# lisa_m.net
KiCad netlist of a schematic drawn in EAGLE
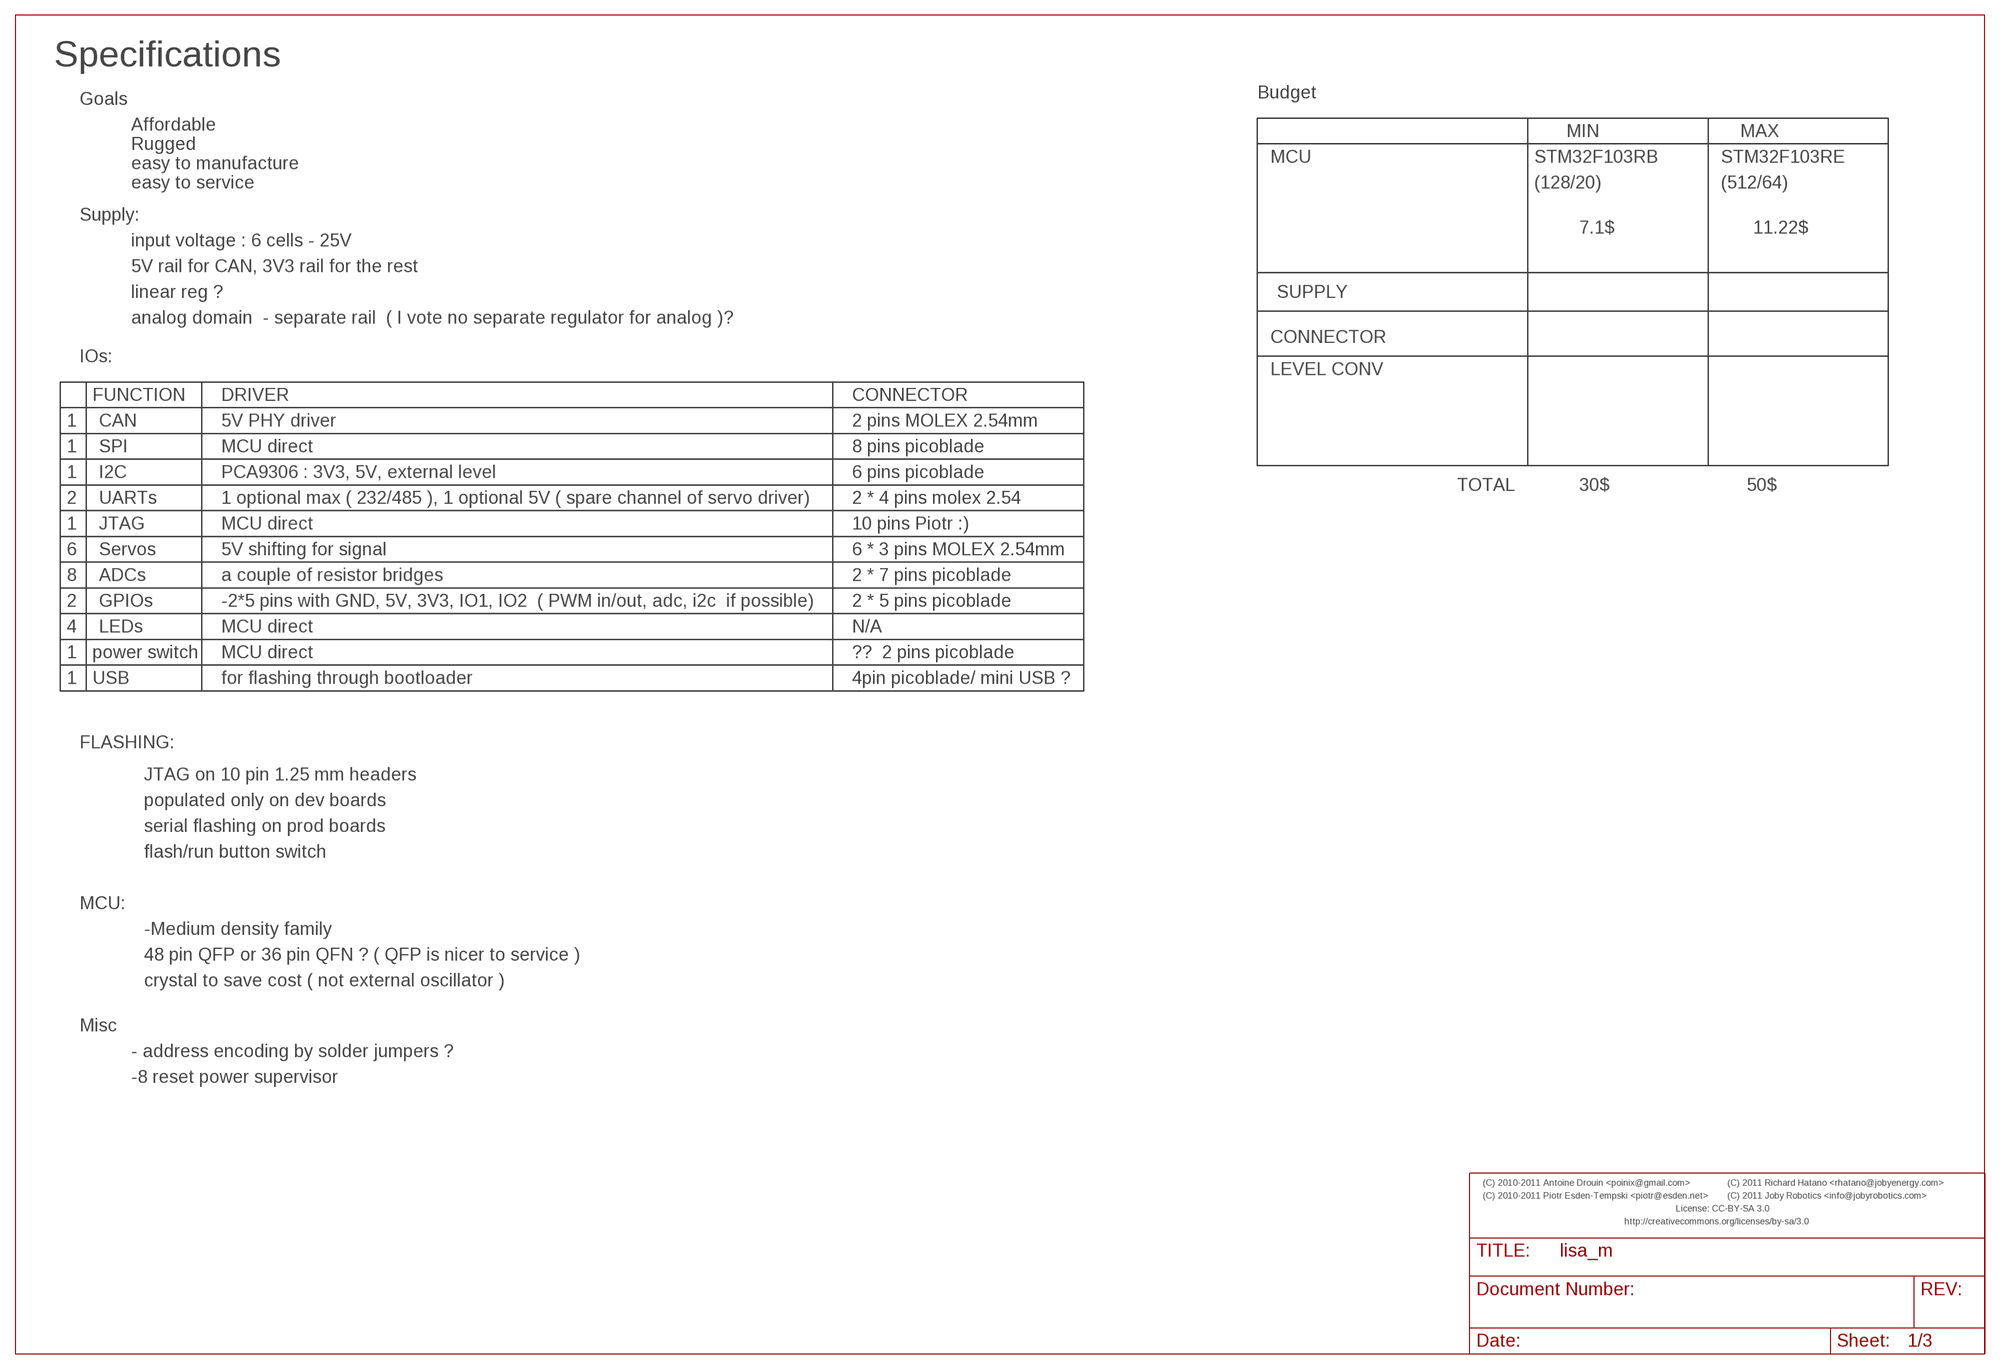
[diagram p0: schematic, sheet 1]
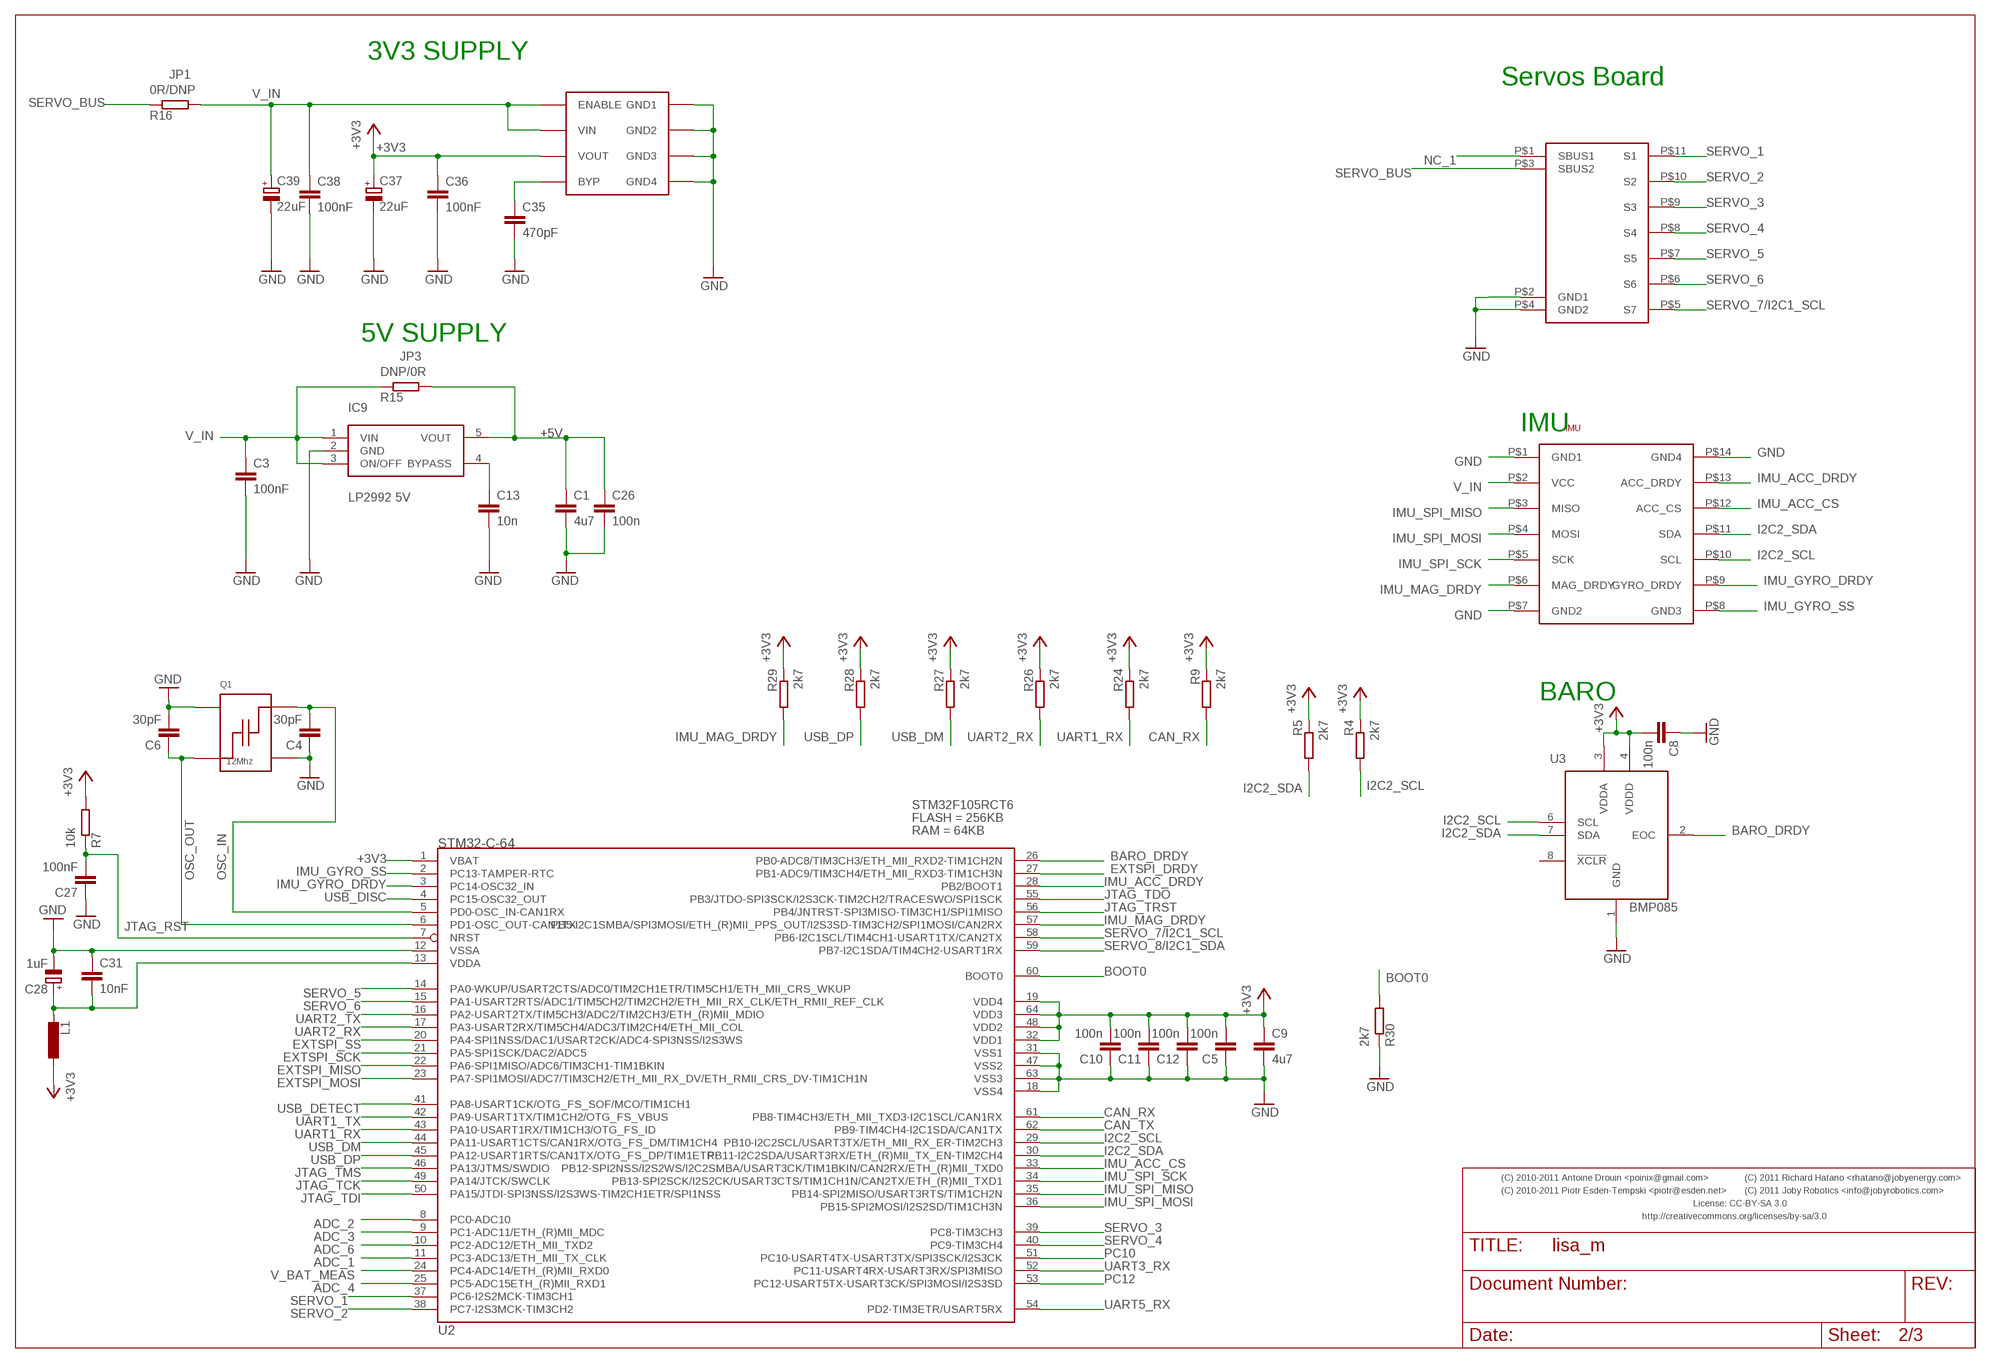
[diagram p1: schematic, sheet 2]
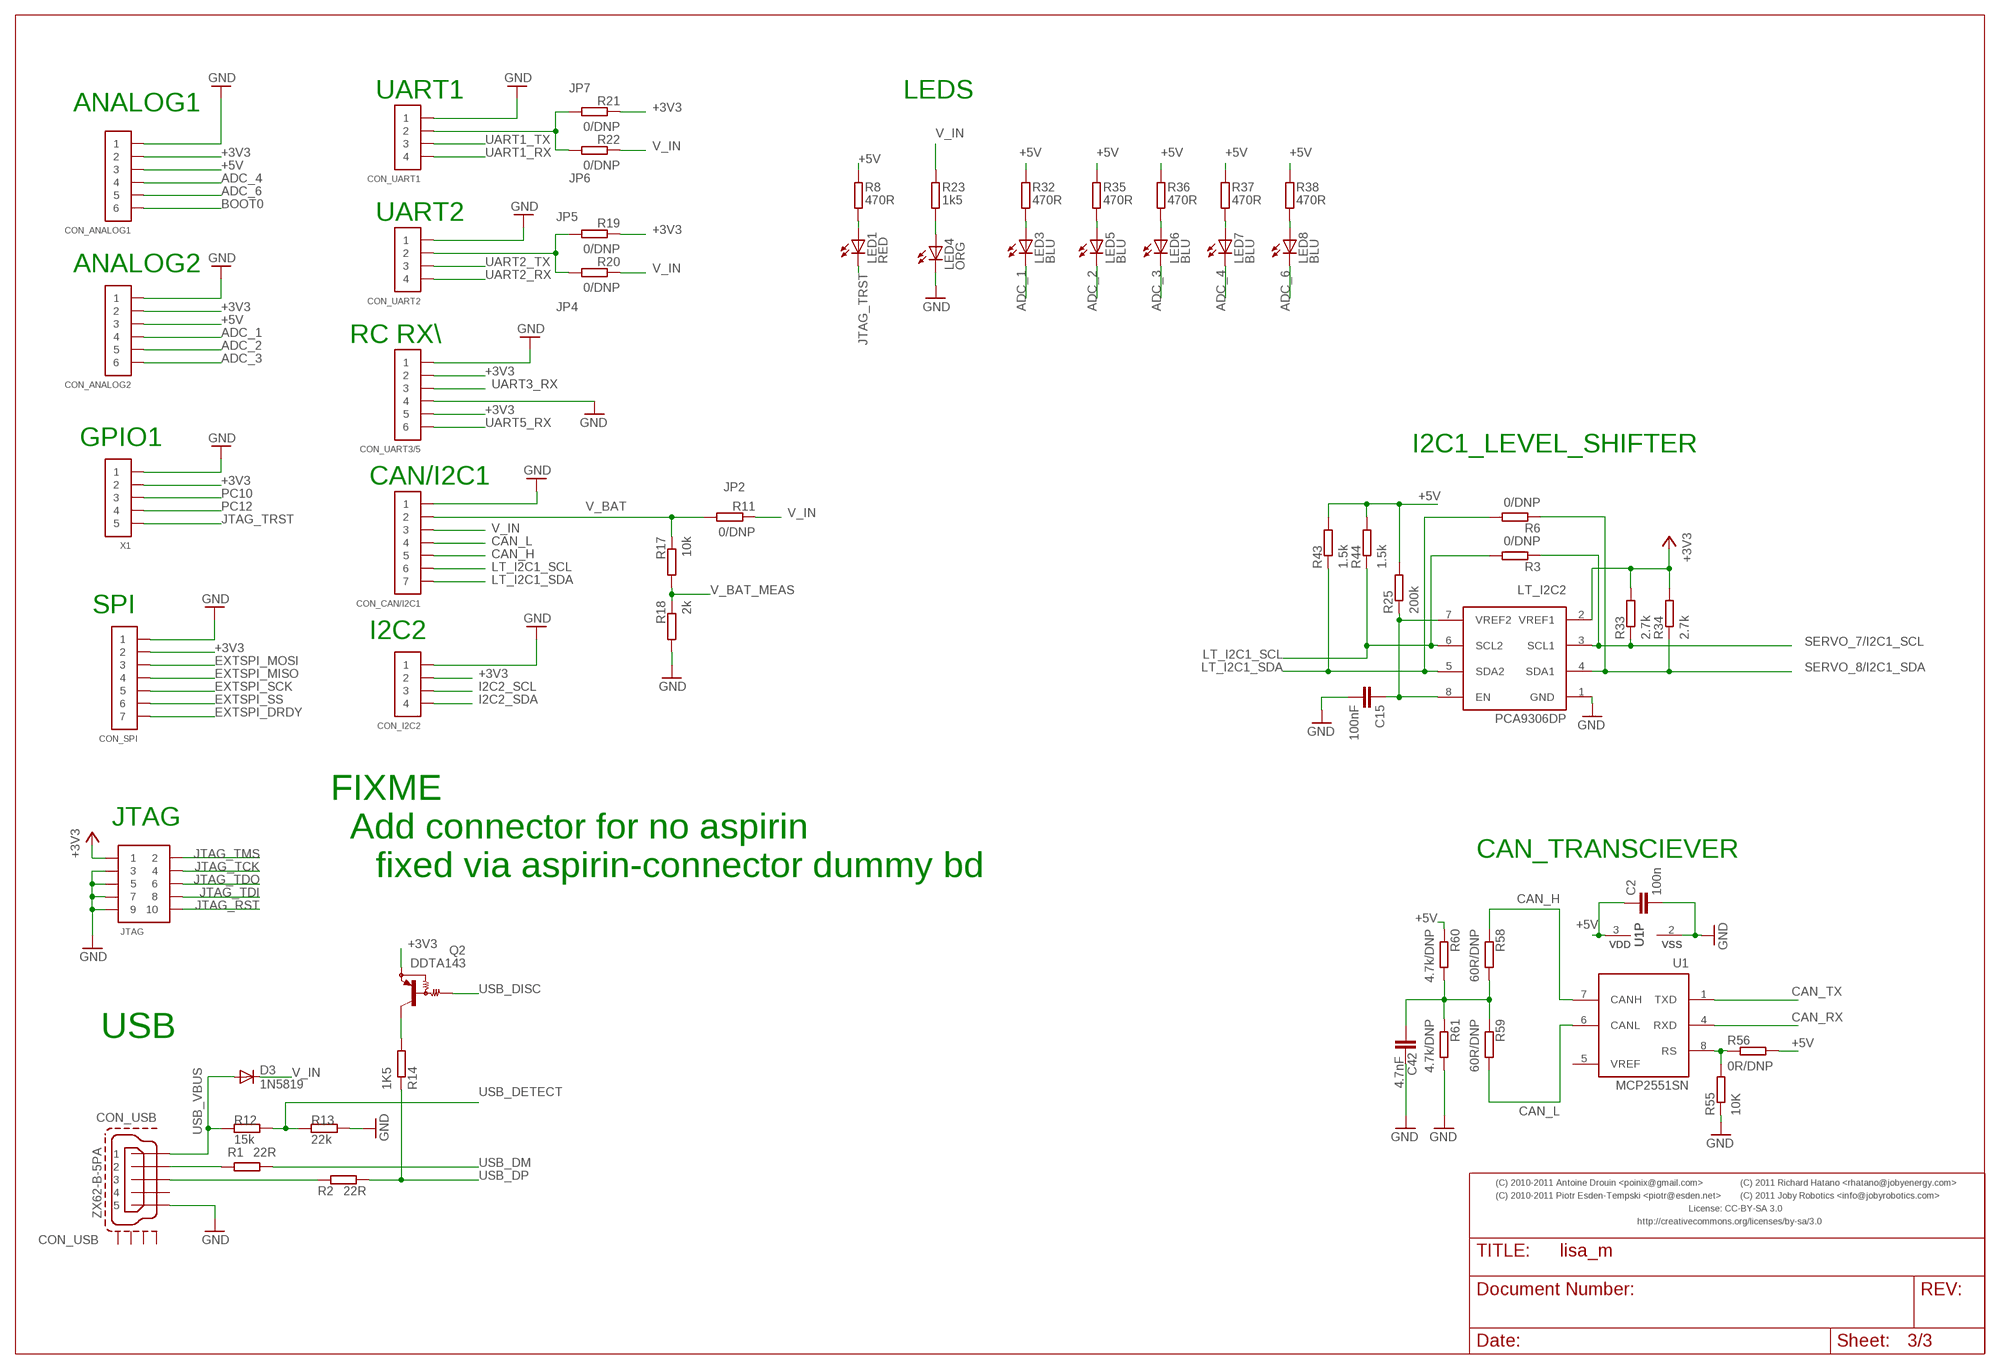
[diagram p2: schematic, sheet 3]

(export (version "E")
  (design (tool "Eeschema 10.0.6"))
  (components
    (comp (ref "C2")
      (value "100n")
      (footprint "eagle-import:0402-CAP")
      (libsource (lib "eagle-import") (part "CAPACITOR-0402"))
    )
    (comp (ref "C15")
      (value "100nF")
      (footprint "eagle-import:0402-CAP")
      (libsource (lib "eagle-import") (part "CAPACITOR-0402"))
    )
    (comp (ref "C42")
      (value "4.7nF")
      (footprint "eagle-import:0603-CAP")
      (libsource (lib "eagle-import") (part "CAPACITOR-0603"))
    )
    (comp (ref "CON_ANALOG1")
      (value "CONN_6-1-53398")
      (footprint "eagle-import:PB-53398-06")
      (libsource (lib "eagle-import") (part "pel_molex_CONN_6-1-53398"))
    )
    (comp (ref "CON_ANALOG2")
      (value "CONN_6-1-53398")
      (footprint "eagle-import:PB-53398-06")
      (libsource (lib "eagle-import") (part "pel_molex_CONN_6-1-53398"))
    )
    (comp (ref "CON_CAN/I2C1")
      (value "CONN_7-1-53261")
      (footprint "eagle-import:PB-53261-07")
      (libsource (lib "eagle-import") (part "CONN_7-1-53261"))
    )
    (comp (ref "CON_I2C2")
      (value "CONN_4-1-53398")
      (footprint "eagle-import:PB-53398-04")
      (libsource (lib "eagle-import") (part "CONN_4-1-53398"))
    )
    (comp (ref "CON_SPI")
      (value "CONN_7-1-53398")
      (footprint "eagle-import:PB-53398-07")
      (libsource (lib "eagle-import") (part "CONN_7-1-53398"))
    )
    (comp (ref "CON_UART1")
      (value "CONN_4-1-53398")
      (footprint "eagle-import:PB-53398-04")
      (libsource (lib "eagle-import") (part "CONN_4-1-53398"))
    )
    (comp (ref "CON_UART2")
      (value "CONN_4-1-53398")
      (footprint "eagle-import:PB-53398-04")
      (libsource (lib "eagle-import") (part "CONN_4-1-53398"))
    )
    (comp (ref "CON_UART3/5")
      (value "CONN_6-1PB-53398-06_SMALL")
      (footprint "eagle-import:PB-53398-06")
      (libsource (lib "eagle-import") (part "CONN_6-1PB-53398-06_SMALL"))
    )
    (comp (ref "CON_USB")
      (value "ZX62-B-5PA")
      (footprint "eagle-import:ZX62-B-5PA")
      (libsource (lib "eagle-import") (part "ZX62-B-5PA"))
    )
    (comp (ref "D3")
      (value "1N5819")
      (footprint "eagle-import:MICROMELF-R")
      (libsource (lib "eagle-import") (part "DIODE-MICROMELF-R"))
    )
    (comp (ref "JTAG")
      (value "PIN_HDR_EDG_1.27MM_5-2")
      (footprint "eagle-import:FTSH-105-DV")
      (libsource (lib "eagle-import") (part "CONN_5-2-FTSH-V"))
    )
    (comp (ref "LED1")
      (value "RED")
      (footprint "eagle-import:0402-LED")
      (libsource (lib "eagle-import") (part "LED-0402"))
    )
    (comp (ref "LED3")
      (value "BLU")
      (footprint "eagle-import:0402-LED")
      (libsource (lib "eagle-import") (part "LED-0402"))
    )
    (comp (ref "LED4")
      (value "ORG")
      (footprint "eagle-import:0402-LED")
      (libsource (lib "eagle-import") (part "LED-0402"))
    )
    (comp (ref "LED5")
      (value "BLU")
      (footprint "eagle-import:0402-LED")
      (libsource (lib "eagle-import") (part "LED-0402"))
    )
    (comp (ref "LED6")
      (value "BLU")
      (footprint "eagle-import:0402-LED")
      (libsource (lib "eagle-import") (part "LED-0402"))
    )
    (comp (ref "LED7")
      (value "BLU")
      (footprint "eagle-import:0402-LED")
      (libsource (lib "eagle-import") (part "LED-0402"))
    )
    (comp (ref "LED8")
      (value "BLU")
      (footprint "eagle-import:0402-LED")
      (libsource (lib "eagle-import") (part "LED-0402"))
    )
    (comp (ref "LT_I2C2")
      (value "PCA9306DP")
      (footprint "eagle-import:TSSOP_B3")
      (libsource (lib "eagle-import") (part "PCA9306DP"))
    )
    (comp (ref "Q2")
      (value "DDTA143")
      (footprint "eagle-import:SOT23")
      (libsource (lib "eagle-import") (part "MUN2111SOT23"))
    )
    (comp (ref "R1")
      (value "22R")
      (footprint "eagle-import:0402-RES")
      (libsource (lib "eagle-import") (part "RESISTOR-0402"))
    )
    (comp (ref "R2")
      (value "22R")
      (footprint "eagle-import:0402-RES")
      (libsource (lib "eagle-import") (part "RESISTOR-0402"))
    )
    (comp (ref "R3")
      (value "0/DNP")
      (footprint "eagle-import:0603-RES")
      (libsource (lib "eagle-import") (part "RESISTOR-0603"))
    )
    (comp (ref "R6")
      (value "0/DNP")
      (footprint "eagle-import:0603-RES")
      (libsource (lib "eagle-import") (part "RESISTOR-0603"))
    )
    (comp (ref "R8")
      (value "470R")
      (footprint "eagle-import:0402-RES")
      (libsource (lib "eagle-import") (part "RESISTOR-0402"))
    )
    (comp (ref "R11")
      (value "0/DNP")
      (footprint "eagle-import:0402-RES")
      (libsource (lib "eagle-import") (part "RESISTOR-0402"))
    )
    (comp (ref "R12")
      (value "15k")
      (footprint "eagle-import:0402-RES")
      (libsource (lib "eagle-import") (part "RESISTOR-0402"))
    )
    (comp (ref "R13")
      (value "22k")
      (footprint "eagle-import:0402-RES")
      (libsource (lib "eagle-import") (part "RESISTOR-0402"))
    )
    (comp (ref "R14")
      (value "1K5")
      (footprint "eagle-import:0402-RES")
      (libsource (lib "eagle-import") (part "RESISTOR-0402"))
    )
    (comp (ref "R17")
      (value "10k")
      (footprint "eagle-import:0402-RES")
      (libsource (lib "eagle-import") (part "RESISTOR-0402"))
    )
    (comp (ref "R18")
      (value "2k")
      (footprint "eagle-import:0402-RES")
      (libsource (lib "eagle-import") (part "RESISTOR-0402"))
    )
    (comp (ref "R19")
      (value "0/DNP")
      (footprint "eagle-import:0402-RES")
      (libsource (lib "eagle-import") (part "RESISTOR-0402"))
    )
    (comp (ref "R20")
      (value "0/DNP")
      (footprint "eagle-import:0402-RES")
      (libsource (lib "eagle-import") (part "RESISTOR-0402"))
    )
    (comp (ref "R21")
      (value "0/DNP")
      (footprint "eagle-import:0402-RES")
      (libsource (lib "eagle-import") (part "RESISTOR-0402"))
    )
    (comp (ref "R22")
      (value "0/DNP")
      (footprint "eagle-import:0402-RES")
      (libsource (lib "eagle-import") (part "RESISTOR-0402"))
    )
    (comp (ref "R23")
      (value "1k5")
      (footprint "eagle-import:0402-RES")
      (libsource (lib "eagle-import") (part "RESISTOR-0402"))
    )
    (comp (ref "R25")
      (value "200k")
      (footprint "eagle-import:0402-RES")
      (libsource (lib "eagle-import") (part "RESISTOR-0402"))
    )
    (comp (ref "R32")
      (value "470R")
      (footprint "eagle-import:0402-RES")
      (libsource (lib "eagle-import") (part "RESISTOR-0402"))
    )
    (comp (ref "R33")
      (value "2.7k")
      (footprint "eagle-import:0402-RES")
      (libsource (lib "eagle-import") (part "RESISTOR-0402"))
    )
    (comp (ref "R34")
      (value "2.7k")
      (footprint "eagle-import:0402-RES")
      (libsource (lib "eagle-import") (part "RESISTOR-0402"))
    )
    (comp (ref "R35")
      (value "470R")
      (footprint "eagle-import:0402-RES")
      (libsource (lib "eagle-import") (part "RESISTOR-0402"))
    )
    (comp (ref "R36")
      (value "470R")
      (footprint "eagle-import:0402-RES")
      (libsource (lib "eagle-import") (part "RESISTOR-0402"))
    )
    (comp (ref "R37")
      (value "470R")
      (footprint "eagle-import:0402-RES")
      (libsource (lib "eagle-import") (part "RESISTOR-0402"))
    )
    (comp (ref "R38")
      (value "470R")
      (footprint "eagle-import:0402-RES")
      (libsource (lib "eagle-import") (part "RESISTOR-0402"))
    )
    (comp (ref "R43")
      (value "1.5k")
      (footprint "eagle-import:0402-RES")
      (libsource (lib "eagle-import") (part "RESISTOR-0402"))
    )
    (comp (ref "R44")
      (value "1.5k")
      (footprint "eagle-import:0402-RES")
      (libsource (lib "eagle-import") (part "RESISTOR-0402"))
    )
    (comp (ref "R55")
      (value "10K")
      (footprint "eagle-import:0402-RES")
      (libsource (lib "eagle-import") (part "RESISTOR-0402"))
    )
    (comp (ref "R56")
      (value "0R/DNP")
      (footprint "eagle-import:0402-RES")
      (libsource (lib "eagle-import") (part "RESISTOR-0402"))
    )
    (comp (ref "R58")
      (value "60R/DNP")
      (footprint "eagle-import:0402-RES")
      (libsource (lib "eagle-import") (part "RESISTOR-0402"))
    )
    (comp (ref "R59")
      (value "60R/DNP")
      (footprint "eagle-import:0402-RES")
      (libsource (lib "eagle-import") (part "RESISTOR-0402"))
    )
    (comp (ref "R60")
      (value "4.7k/DNP")
      (footprint "eagle-import:0402-RES")
      (libsource (lib "eagle-import") (part "RESISTOR-0402"))
    )
    (comp (ref "R61")
      (value "4.7k/DNP")
      (footprint "eagle-import:0402-RES")
      (libsource (lib "eagle-import") (part "RESISTOR-0402"))
    )
    (comp (ref "U1")
      (value "MCP2551SN")
      (footprint "eagle-import:SO-08")
      (libsource (lib "eagle-import") (part "MCP2551SN"))
    )
    (comp (ref "X1")
      (value "CONN_5-1-53398")
      (footprint "eagle-import:PB-53398-05")
      (libsource (lib "eagle-import") (part "CONN_5-1-53398"))
    )
    (comp (ref "C1")
      (value "4u7")
      (footprint "eagle-import:0805-CAP")
      (libsource (lib "eagle-import") (part "CAPACITOR-0805"))
    )
    (comp (ref "C3")
      (value "100nF")
      (footprint "eagle-import:0603-CAP")
      (libsource (lib "eagle-import") (part "CAPACITOR-0603"))
    )
    (comp (ref "C4")
      (value "30pF")
      (footprint "eagle-import:0402-CAP")
      (libsource (lib "eagle-import") (part "CAPACITOR-0402"))
    )
    (comp (ref "C5")
      (value "100n")
      (footprint "eagle-import:0402-CAP")
      (libsource (lib "eagle-import") (part "CAPACITOR-0402"))
    )
    (comp (ref "C6")
      (value "30pF")
      (footprint "eagle-import:0402-CAP")
      (libsource (lib "eagle-import") (part "CAPACITOR-0402"))
    )
    (comp (ref "C8")
      (value "100n")
      (footprint "eagle-import:0402-CAP")
      (libsource (lib "eagle-import") (part "CAPACITOR-0402"))
    )
    (comp (ref "C9")
      (value "4u7")
      (footprint "eagle-import:0805-CAP")
      (libsource (lib "eagle-import") (part "CAPACITOR-0805"))
    )
    (comp (ref "C10")
      (value "100n")
      (footprint "eagle-import:0402-CAP")
      (libsource (lib "eagle-import") (part "CAPACITOR-0402"))
    )
    (comp (ref "C11")
      (value "100n")
      (footprint "eagle-import:0402-CAP")
      (libsource (lib "eagle-import") (part "CAPACITOR-0402"))
    )
    (comp (ref "C12")
      (value "100n")
      (footprint "eagle-import:0402-CAP")
      (libsource (lib "eagle-import") (part "CAPACITOR-0402"))
    )
    (comp (ref "C13")
      (value "10n")
      (footprint "eagle-import:0402-CAP")
      (libsource (lib "eagle-import") (part "CAPACITOR-0402"))
    )
    (comp (ref "C26")
      (value "100n")
      (footprint "eagle-import:0603-CAP")
      (libsource (lib "eagle-import") (part "CAPACITOR-0603"))
    )
    (comp (ref "C27")
      (value "100nF")
      (footprint "eagle-import:0402-CAP")
      (libsource (lib "eagle-import") (part "CAPACITOR-0402"))
    )
    (comp (ref "C28")
      (value "1uF")
      (footprint "eagle-import:0603-POL-CAP")
      (libsource (lib "eagle-import") (part "CAPACITOR-POL-0603"))
    )
    (comp (ref "C31")
      (value "10nF")
      (footprint "eagle-import:0402-CAP")
      (libsource (lib "eagle-import") (part "CAPACITOR-0402"))
    )
    (comp (ref "C35")
      (value "470pF")
      (footprint "eagle-import:0402-CAP")
      (libsource (lib "eagle-import") (part "CAPACITOR-0402"))
    )
    (comp (ref "C36")
      (value "100nF")
      (footprint "eagle-import:0603-CAP")
      (libsource (lib "eagle-import") (part "CAPACITOR-0603"))
    )
    (comp (ref "C37")
      (value "22uF")
      (footprint "eagle-import:3528_B")
      (libsource (lib "eagle-import") (part "CAPACITOR-POLB"))
    )
    (comp (ref "C38")
      (value "100nF")
      (footprint "eagle-import:0402-CAP")
      (libsource (lib "eagle-import") (part "CAPACITOR-0402"))
    )
    (comp (ref "C39")
      (value "22uF")
      (footprint "eagle-import:3528_B")
      (libsource (lib "eagle-import") (part "CAPACITOR-POLB"))
    )
    (comp (ref "IC9")
      (value "LP2992 5V")
      (footprint "eagle-import:SOT23-5")
      (libsource (lib "eagle-import") (part "LP2992"))
    )
    (comp (ref "IMU")
      (value "ASPIRIN")
      (footprint "eagle-import:ASPIRIN_1")
      (libsource (lib "eagle-import") (part "ASPIRIN"))
    )
    (comp (ref "L1")
      (value "INDUCTOR-0603")
      (footprint "eagle-import:0603-IND")
      (libsource (lib "eagle-import") (part "INDUCTOR-0603"))
    )
    (comp (ref "Q1")
      (value "12Mhz")
      (footprint "eagle-import:ABM8")
      (libsource (lib "eagle-import") (part "ABM8"))
    )
    (comp (ref "R4")
      (value "2k7")
      (footprint "eagle-import:0402-RES")
      (libsource (lib "eagle-import") (part "RESISTOR-0402"))
    )
    (comp (ref "R5")
      (value "2k7")
      (footprint "eagle-import:0402-RES")
      (libsource (lib "eagle-import") (part "RESISTOR-0402"))
    )
    (comp (ref "R7")
      (value "10k")
      (footprint "eagle-import:0402-RES")
      (libsource (lib "eagle-import") (part "RESISTOR-0402"))
    )
    (comp (ref "R9")
      (value "2k7")
      (footprint "eagle-import:0402-RES")
      (libsource (lib "eagle-import") (part "RESISTOR-0402"))
    )
    (comp (ref "R15")
      (value "DNP/0R")
      (footprint "eagle-import:0402-RES")
      (libsource (lib "eagle-import") (part "RESISTOR-0402"))
    )
    (comp (ref "R16")
      (value "0R/DNP")
      (footprint "eagle-import:0402-RES")
      (libsource (lib "eagle-import") (part "RESISTOR-0402"))
    )
    (comp (ref "R24")
      (value "2k7")
      (footprint "eagle-import:0402-RES")
      (libsource (lib "eagle-import") (part "RESISTOR-0402"))
    )
    (comp (ref "R26")
      (value "2k7")
      (footprint "eagle-import:0402-RES")
      (libsource (lib "eagle-import") (part "RESISTOR-0402"))
    )
    (comp (ref "R27")
      (value "2k7")
      (footprint "eagle-import:0402-RES")
      (libsource (lib "eagle-import") (part "RESISTOR-0402"))
    )
    (comp (ref "R28")
      (value "2k7")
      (footprint "eagle-import:0402-RES")
      (libsource (lib "eagle-import") (part "RESISTOR-0402"))
    )
    (comp (ref "R29")
      (value "2k7")
      (footprint "eagle-import:0402-RES")
      (libsource (lib "eagle-import") (part "RESISTOR-0402"))
    )
    (comp (ref "R30")
      (value "2k7")
      (footprint "eagle-import:0402-RES")
      (libsource (lib "eagle-import") (part "RESISTOR-0402"))
    )
    (comp (ref "U$1")
      (value "LISA_M_VBOARD")
      (footprint "eagle-import:LISA_M_VBOARD")
      (libsource (lib "eagle-import") (part "LISA_M_VBOARD"))
    )
    (comp (ref "U2")
      (value "STM32-C-64")
      (footprint "eagle-import:LQFP64")
      (fields
        (field (name "FLASH") "256KB")
        (field (name "PART_NR") "STM32F105RCT6")
        (field (name "RAM") "64KB")
      )
      (libsource (lib "eagle-import") (part "STM32-C-64"))
    )
    (comp (ref "U3")
      (value "BMP085")
      (footprint "eagle-import:LCC8")
      (libsource (lib "eagle-import") (part "BMP085"))
    )
    (comp (ref "VREG1")
      (value "MIC5209")
      (footprint "eagle-import:SOIC8")
      (libsource (lib "eagle-import") (part "MIC5209"))
    )
  )
  (nets
    (net (code "1") (name "+3V3") (class "Default")
      (node (ref "C10") (pin "P$2") (pinfunction "2_P$2") (pintype "passive"))
      (node (ref "C11") (pin "P$2") (pinfunction "2_P$2") (pintype "passive"))
      (node (ref "C12") (pin "P$2") (pinfunction "2_P$2") (pintype "passive"))
      (node (ref "C36") (pin "P$1") (pinfunction "1_P$1") (pintype "passive"))
      (node (ref "C37") (pin "+") (pinfunction "+_+") (pintype "passive"))
      (node (ref "C5") (pin "P$2") (pinfunction "2_P$2") (pintype "passive"))
      (node (ref "C8") (pin "P$2") (pinfunction "2_P$2") (pintype "passive"))
      (node (ref "C9") (pin "P$1") (pinfunction "1_P$1") (pintype "passive"))
      (node (ref "CON_ANALOG1") (pin "2") (pinfunction "2_2") (pintype "bidirectional"))
      (node (ref "CON_ANALOG2") (pin "2") (pinfunction "2_2") (pintype "bidirectional"))
      (node (ref "CON_I2C2") (pin "2") (pinfunction "2_2") (pintype "bidirectional"))
      (node (ref "CON_SPI") (pin "2") (pinfunction "2_2") (pintype "bidirectional"))
      (node (ref "CON_UART3/5") (pin "2") (pinfunction "2_2") (pintype "bidirectional"))
      (node (ref "CON_UART3/5") (pin "5") (pinfunction "5_5") (pintype "bidirectional"))
      (node (ref "JTAG") (pin "1") (pinfunction "1_1") (pintype "bidirectional"))
      (node (ref "L1") (pin "P$1") (pinfunction "1_P$1") (pintype "passive"))
      (node (ref "LT_I2C2") (pin "2") (pinfunction "VREF1_2") (pintype "bidirectional"))
      (node (ref "Q2") (pin "2") (pinfunction "E_2") (pintype "passive"))
      (node (ref "R19") (pin "P$1") (pinfunction "1_P$1") (pintype "passive"))
      (node (ref "R21") (pin "P$1") (pinfunction "1_P$1") (pintype "passive"))
      (node (ref "R24") (pin "P$1") (pinfunction "1_P$1") (pintype "passive"))
      (node (ref "R26") (pin "P$1") (pinfunction "1_P$1") (pintype "passive"))
      (node (ref "R27") (pin "P$1") (pinfunction "1_P$1") (pintype "passive"))
      (node (ref "R28") (pin "P$1") (pinfunction "1_P$1") (pintype "passive"))
      (node (ref "R29") (pin "P$1") (pinfunction "1_P$1") (pintype "passive"))
      (node (ref "R33") (pin "P$2") (pinfunction "2_P$2") (pintype "passive"))
      (node (ref "R34") (pin "P$2") (pinfunction "2_P$2") (pintype "passive"))
      (node (ref "R4") (pin "P$1") (pinfunction "1_P$1") (pintype "passive"))
      (node (ref "R5") (pin "P$1") (pinfunction "1_P$1") (pintype "passive"))
      (node (ref "R7") (pin "P$2") (pinfunction "2_P$2") (pintype "passive"))
      (node (ref "R9") (pin "P$1") (pinfunction "1_P$1") (pintype "passive"))
      (node (ref "U2") (pin "1") (pinfunction "VBAT_1") (pintype "power_in"))
      (node (ref "U2") (pin "19") (pinfunction "VDD4_19") (pintype "bidirectional"))
      (node (ref "U2") (pin "32") (pinfunction "VDD1_32") (pintype "power_in"))
      (node (ref "U2") (pin "48") (pinfunction "VDD2_48") (pintype "power_in"))
      (node (ref "U2") (pin "64") (pinfunction "VDD3_64") (pintype "power_in"))
      (node (ref "U3") (pin "3") (pinfunction "VDDA_3") (pintype "power_in"))
      (node (ref "U3") (pin "4") (pinfunction "VDDD_4") (pintype "power_in"))
      (node (ref "VREG1") (pin "3") (pinfunction "VOUT_3") (pintype "bidirectional"))
      (node (ref "X1") (pin "2") (pinfunction "2_2") (pintype "bidirectional"))
    )
    (net (code "2") (name "+5V") (class "Default")
      (node (ref "C1") (pin "P$1") (pinfunction "1_P$1") (pintype "passive"))
      (node (ref "C2") (pin "P$1") (pinfunction "1_P$1") (pintype "passive"))
      (node (ref "C26") (pin "P$1") (pinfunction "1_P$1") (pintype "passive"))
      (node (ref "CON_ANALOG1") (pin "3") (pinfunction "3_3") (pintype "bidirectional"))
      (node (ref "CON_ANALOG2") (pin "3") (pinfunction "3_3") (pintype "bidirectional"))
      (node (ref "IC9") (pin "5") (pinfunction "VOUT_5") (pintype "bidirectional"))
      (node (ref "R15") (pin "P$2") (pinfunction "2_P$2") (pintype "passive"))
      (node (ref "R25") (pin "P$2") (pinfunction "2_P$2") (pintype "passive"))
      (node (ref "R32") (pin "P$2") (pinfunction "2_P$2") (pintype "passive"))
      (node (ref "R35") (pin "P$2") (pinfunction "2_P$2") (pintype "passive"))
      (node (ref "R36") (pin "P$2") (pinfunction "2_P$2") (pintype "passive"))
      (node (ref "R37") (pin "P$2") (pinfunction "2_P$2") (pintype "passive"))
      (node (ref "R38") (pin "P$2") (pinfunction "2_P$2") (pintype "passive"))
      (node (ref "R43") (pin "P$2") (pinfunction "2_P$2") (pintype "passive"))
      (node (ref "R44") (pin "P$2") (pinfunction "2_P$2") (pintype "passive"))
      (node (ref "R56") (pin "P$2") (pinfunction "2_P$2") (pintype "passive"))
      (node (ref "R60") (pin "P$1") (pinfunction "1_P$1") (pintype "passive"))
      (node (ref "R8") (pin "P$2") (pinfunction "2_P$2") (pintype "passive"))
      (node (ref "U1") (pin "3") (pinfunction "VDD_3") (pintype "power_in"))
    )
    (net (code "3") (name "ADC_1") (class "Default")
      (node (ref "CON_ANALOG2") (pin "4") (pinfunction "4_4") (pintype "bidirectional"))
      (node (ref "LED3") (pin "C") (pinfunction "C_C") (pintype "passive"))
      (node (ref "U2") (pin "11") (pinfunction "PC3-ADC13/ETH_MII_TX_CLK_11") (pintype "bidirectional"))
    )
    (net (code "4") (name "ADC_2") (class "Default")
      (node (ref "CON_ANALOG2") (pin "5") (pinfunction "5_5") (pintype "bidirectional"))
      (node (ref "LED5") (pin "C") (pinfunction "C_C") (pintype "passive"))
      (node (ref "U2") (pin "8") (pinfunction "PC0-ADC10_8") (pintype "bidirectional"))
    )
    (net (code "5") (name "ADC_3") (class "Default")
      (node (ref "CON_ANALOG2") (pin "6") (pinfunction "6_6") (pintype "bidirectional"))
      (node (ref "LED6") (pin "C") (pinfunction "C_C") (pintype "passive"))
      (node (ref "U2") (pin "9") (pinfunction "PC1-ADC11/ETH_(R)MII_MDC_9") (pintype "bidirectional"))
    )
    (net (code "6") (name "ADC_4") (class "Default")
      (node (ref "CON_ANALOG1") (pin "4") (pinfunction "4_4") (pintype "bidirectional"))
      (node (ref "LED7") (pin "C") (pinfunction "C_C") (pintype "passive"))
      (node (ref "U2") (pin "25") (pinfunction "PC5-ADC15ETH_(R)MII_RXD1_25") (pintype "bidirectional"))
    )
    (net (code "7") (name "ADC_6") (class "Default")
      (node (ref "CON_ANALOG1") (pin "5") (pinfunction "5_5") (pintype "bidirectional"))
      (node (ref "LED8") (pin "C") (pinfunction "C_C") (pintype "passive"))
      (node (ref "U2") (pin "10") (pinfunction "PC2-ADC12/ETH_MII_TXD2_10") (pintype "bidirectional"))
    )
    (net (code "8") (name "BARO_DRDY") (class "Default")
      (node (ref "U2") (pin "26") (pinfunction "PB0-ADC8/TIM3CH3/ETH_MII_RXD2-TIM1CH2N_26") (pintype "bidirectional"))
      (node (ref "U3") (pin "2") (pinfunction "EOC_2") (pintype "output"))
    )
    (net (code "9") (name "BOOT0") (class "Default")
      (node (ref "CON_ANALOG1") (pin "6") (pinfunction "6_6") (pintype "bidirectional"))
      (node (ref "R30") (pin "P$2") (pinfunction "2_P$2") (pintype "passive"))
      (node (ref "U2") (pin "60") (pinfunction "BOOT0_60") (pintype "input"))
    )
    (net (code "10") (name "CAN_H") (class "Default")
      (node (ref "CON_CAN/I2C1") (pin "5") (pinfunction "5_5") (pintype "bidirectional"))
      (node (ref "R58") (pin "P$1") (pinfunction "1_P$1") (pintype "passive"))
      (node (ref "U1") (pin "7") (pinfunction "CANH_7") (pintype "bidirectional"))
    )
    (net (code "11") (name "CAN_L") (class "Default")
      (node (ref "CON_CAN/I2C1") (pin "4") (pinfunction "4_4") (pintype "bidirectional"))
      (node (ref "R59") (pin "P$2") (pinfunction "2_P$2") (pintype "passive"))
      (node (ref "U1") (pin "6") (pinfunction "CANL_6") (pintype "bidirectional"))
    )
    (net (code "12") (name "CAN_RX") (class "Default")
      (node (ref "R9") (pin "P$2") (pinfunction "2_P$2") (pintype "passive"))
      (node (ref "U1") (pin "4") (pinfunction "RXD_4") (pintype "output"))
      (node (ref "U2") (pin "61") (pinfunction "PB8-TIM4CH3/ETH_MII_TXD3-I2C1SCL/CAN1RX_61") (pintype "bidirectional"))
    )
    (net (code "13") (name "CAN_TX") (class "Default")
      (node (ref "U1") (pin "1") (pinfunction "TXD_1") (pintype "input"))
      (node (ref "U2") (pin "62") (pinfunction "PB9-TIM4CH4-I2C1SDA/CAN1TX_62") (pintype "bidirectional"))
    )
    (net (code "14") (name "EXTSPI_DRDY") (class "Default")
      (node (ref "CON_SPI") (pin "7") (pinfunction "7_7") (pintype "bidirectional"))
      (node (ref "U2") (pin "27") (pinfunction "PB1-ADC9/TIM3CH4/ETH_MII_RXD3-TIM1CH3N_27") (pintype "bidirectional"))
    )
    (net (code "15") (name "EXTSPI_MISO") (class "Default")
      (node (ref "CON_SPI") (pin "4") (pinfunction "4_4") (pintype "bidirectional"))
      (node (ref "U2") (pin "22") (pinfunction "PA6-SPI1MISO/ADC6/TIM3CH1-TIM1BKIN_22") (pintype "bidirectional"))
    )
    (net (code "16") (name "EXTSPI_MOSI") (class "Default")
      (node (ref "CON_SPI") (pin "3") (pinfunction "3_3") (pintype "bidirectional"))
      (node (ref "U2") (pin "23") (pinfunction "PA7-SPI1MOSI/ADC7/TIM3CH2/ETH_MII_RX_DV/ETH_RMII_CRS_DV-TIM1CH1N_23") (pintype "bidirectional"))
    )
    (net (code "17") (name "EXTSPI_SCK") (class "Default")
      (node (ref "CON_SPI") (pin "5") (pinfunction "5_5") (pintype "bidirectional"))
      (node (ref "U2") (pin "21") (pinfunction "PA5-SPI1SCK/DAC2/ADC5_21") (pintype "bidirectional"))
    )
    (net (code "18") (name "EXTSPI_SS") (class "Default")
      (node (ref "CON_SPI") (pin "6") (pinfunction "6_6") (pintype "bidirectional"))
      (node (ref "U2") (pin "20") (pinfunction "PA4-SPI1NSS/DAC1/USART2CK/ADC4-SPI3NSS/I2S3WS_20") (pintype "bidirectional"))
    )
    (net (code "19") (name "GND") (class "Default")
      (node (ref "C1") (pin "P$2") (pinfunction "2_P$2") (pintype "passive"))
      (node (ref "C10") (pin "P$1") (pinfunction "1_P$1") (pintype "passive"))
      (node (ref "C11") (pin "P$1") (pinfunction "1_P$1") (pintype "passive"))
      (node (ref "C12") (pin "P$1") (pinfunction "1_P$1") (pintype "passive"))
      (node (ref "C13") (pin "P$2") (pinfunction "2_P$2") (pintype "passive"))
      (node (ref "C15") (pin "P$2") (pinfunction "2_P$2") (pintype "passive"))
      (node (ref "C2") (pin "P$2") (pinfunction "2_P$2") (pintype "passive"))
      (node (ref "C26") (pin "P$2") (pinfunction "2_P$2") (pintype "passive"))
      (node (ref "C27") (pin "P$1") (pinfunction "1_P$1") (pintype "passive"))
      (node (ref "C28") (pin "-") (pinfunction "-_-") (pintype "passive"))
      (node (ref "C3") (pin "P$2") (pinfunction "2_P$2") (pintype "passive"))
      (node (ref "C31") (pin "P$1") (pinfunction "1_P$1") (pintype "passive"))
      (node (ref "C35") (pin "P$2") (pinfunction "2_P$2") (pintype "passive"))
      (node (ref "C36") (pin "P$2") (pinfunction "2_P$2") (pintype "passive"))
      (node (ref "C37") (pin "-") (pinfunction "-_-") (pintype "passive"))
      (node (ref "C38") (pin "P$2") (pinfunction "2_P$2") (pintype "passive"))
      (node (ref "C39") (pin "-") (pinfunction "-_-") (pintype "passive"))
      (node (ref "C4") (pin "P$1") (pinfunction "1_P$1") (pintype "passive"))
      (node (ref "C42") (pin "P$1") (pinfunction "1_P$1") (pintype "passive"))
      (node (ref "C5") (pin "P$1") (pinfunction "1_P$1") (pintype "passive"))
      (node (ref "C6") (pin "P$2") (pinfunction "2_P$2") (pintype "passive"))
      (node (ref "C8") (pin "P$1") (pinfunction "1_P$1") (pintype "passive"))
      (node (ref "C9") (pin "P$2") (pinfunction "2_P$2") (pintype "passive"))
      (node (ref "CON_ANALOG1") (pin "1") (pinfunction "1_1") (pintype "bidirectional"))
      (node (ref "CON_ANALOG2") (pin "1") (pinfunction "1_1") (pintype "bidirectional"))
      (node (ref "CON_CAN/I2C1") (pin "1") (pinfunction "1_1") (pintype "bidirectional"))
      (node (ref "CON_I2C2") (pin "1") (pinfunction "1_1") (pintype "bidirectional"))
      (node (ref "CON_SPI") (pin "1") (pinfunction "1_1") (pintype "bidirectional"))
      (node (ref "CON_UART1") (pin "1") (pinfunction "1_1") (pintype "bidirectional"))
      (node (ref "CON_UART2") (pin "1") (pinfunction "1_1") (pintype "bidirectional"))
      (node (ref "CON_UART3/5") (pin "1") (pinfunction "1_1") (pintype "bidirectional"))
      (node (ref "CON_UART3/5") (pin "4") (pinfunction "4_4") (pintype "bidirectional"))
      (node (ref "CON_USB") (pin "PIN_5") (pinfunction "5_PIN_5") (pintype "input"))
      (node (ref "IC9") (pin "2") (pinfunction "GND_2") (pintype "bidirectional"))
      (node (ref "IMU") (pin "P$1") (pinfunction "GND1_P$1") (pintype "bidirectional"))
      (node (ref "IMU") (pin "P$14") (pinfunction "GND4_P$14") (pintype "bidirectional"))
      (node (ref "IMU") (pin "P$7") (pinfunction "GND2_P$7") (pintype "bidirectional"))
      (node (ref "JTAG") (pin "3") (pinfunction "3_3") (pintype "bidirectional"))
      (node (ref "JTAG") (pin "5") (pinfunction "5_5") (pintype "bidirectional"))
      (node (ref "JTAG") (pin "7") (pinfunction "7_7") (pintype "bidirectional"))
      (node (ref "JTAG") (pin "9") (pinfunction "9_9") (pintype "bidirectional"))
      (node (ref "LED4") (pin "C") (pinfunction "C_C") (pintype "passive"))
      (node (ref "LT_I2C2") (pin "1") (pinfunction "GND_1") (pintype "bidirectional"))
      (node (ref "Q1") (pin "P$2") (pinfunction "P$2_P$2") (pintype "bidirectional"))
      (node (ref "Q1") (pin "P$4") (pinfunction "P$4_P$4") (pintype "bidirectional"))
      (node (ref "R13") (pin "P$2") (pinfunction "2_P$2") (pintype "passive"))
      (node (ref "R18") (pin "P$2") (pinfunction "2_P$2") (pintype "passive"))
      (node (ref "R30") (pin "P$1") (pinfunction "1_P$1") (pintype "passive"))
      (node (ref "R55") (pin "P$1") (pinfunction "1_P$1") (pintype "passive"))
      (node (ref "R61") (pin "P$2") (pinfunction "2_P$2") (pintype "passive"))
      (node (ref "U$1") (pin "P$2") (pinfunction "GND1_P$2") (pintype "bidirectional"))
      (node (ref "U$1") (pin "P$4") (pinfunction "GND2_P$4") (pintype "bidirectional"))
      (node (ref "U1") (pin "2") (pinfunction "VSS_2") (pintype "power_in"))
      (node (ref "U2") (pin "12") (pinfunction "VSSA_12") (pintype "power_in"))
      (node (ref "U2") (pin "18") (pinfunction "VSS4_18") (pintype "bidirectional"))
      (node (ref "U2") (pin "31") (pinfunction "VSS1_31") (pintype "power_in"))
      (node (ref "U2") (pin "47") (pinfunction "VSS2_47") (pintype "power_in"))
      (node (ref "U2") (pin "63") (pinfunction "VSS3_63") (pintype "power_in"))
      (node (ref "U3") (pin "1") (pinfunction "GND_1") (pintype "power_in"))
      (node (ref "VREG1") (pin "5") (pinfunction "GND4_5") (pintype "bidirectional"))
      (node (ref "VREG1") (pin "6") (pinfunction "GND3_6") (pintype "bidirectional"))
      (node (ref "VREG1") (pin "7") (pinfunction "GND2_7") (pintype "bidirectional"))
      (node (ref "VREG1") (pin "8") (pinfunction "GND1_8") (pintype "bidirectional"))
      (node (ref "X1") (pin "1") (pinfunction "1_1") (pintype "bidirectional"))
    )
    (net (code "20") (name "I2C2_SCL") (class "Default")
      (node (ref "CON_I2C2") (pin "3") (pinfunction "3_3") (pintype "bidirectional"))
      (node (ref "IMU") (pin "P$10") (pinfunction "SCL_P$10") (pintype "bidirectional"))
      (node (ref "R4") (pin "P$2") (pinfunction "2_P$2") (pintype "passive"))
      (node (ref "U2") (pin "29") (pinfunction "PB10-I2C2SCL/USART3TX/ETH_MII_RX_ER-TIM2CH3_29") (pintype "bidirectional"))
      (node (ref "U3") (pin "6") (pinfunction "SCL_6") (pintype "input"))
    )
    (net (code "21") (name "I2C2_SDA") (class "Default")
      (node (ref "CON_I2C2") (pin "4") (pinfunction "4_4") (pintype "bidirectional"))
      (node (ref "IMU") (pin "P$11") (pinfunction "SDA_P$11") (pintype "bidirectional"))
      (node (ref "R5") (pin "P$2") (pinfunction "2_P$2") (pintype "passive"))
      (node (ref "U2") (pin "30") (pinfunction "PB11-I2C2SDA/USART3RX/ETH_(R)MII_TX_EN-TIM2CH4_30") (pintype "bidirectional"))
      (node (ref "U3") (pin "7") (pinfunction "SDA_7") (pintype "bidirectional"))
    )
    (net (code "22") (name "IMU_ACC_CS") (class "Default")
      (node (ref "IMU") (pin "P$12") (pinfunction "ACC_CS_P$12") (pintype "bidirectional"))
      (node (ref "U2") (pin "33") (pinfunction "PB12-SPI2NSS/I2S2WS/I2C2SMBA/USART3CK/TIM1BKIN/CAN2RX/ETH_(R)MII_TXD0_33") (pintype "bidirectional"))
    )
    (net (code "23") (name "IMU_ACC_DRDY") (class "Default")
      (node (ref "IMU") (pin "P$13") (pinfunction "ACC_DRDY_P$13") (pintype "bidirectional"))
      (node (ref "U2") (pin "28") (pinfunction "PB2/BOOT1_28") (pintype "bidirectional"))
    )
    (net (code "24") (name "IMU_GYRO_DRDY") (class "Default")
      (node (ref "IMU") (pin "P$9") (pinfunction "GYRO_DRDY_P$9") (pintype "bidirectional"))
      (node (ref "U2") (pin "3") (pinfunction "PC14-OSC32_IN_3") (pintype "bidirectional"))
    )
    (net (code "25") (name "IMU_GYRO_SS") (class "Default")
      (node (ref "IMU") (pin "P$8") (pinfunction "GND3_P$8") (pintype "bidirectional"))
      (node (ref "U2") (pin "2") (pinfunction "PC13-TAMPER-RTC_2") (pintype "bidirectional"))
    )
    (net (code "26") (name "IMU_MAG_DRDY") (class "Default")
      (node (ref "IMU") (pin "P$6") (pinfunction "MAG_DRDY_P$6") (pintype "bidirectional"))
      (node (ref "R29") (pin "P$2") (pinfunction "2_P$2") (pintype "passive"))
      (node (ref "U2") (pin "57") (pinfunction "PB5-I2C1SMBA/SPI3MOSI/ETH_(R)MII_PPS_OUT/I2S3SD-TIM3CH2/SPI1MOSI/CAN2RX_57") (pintype "bidirectional"))
    )
    (net (code "27") (name "IMU_SPI_MISO") (class "Default")
      (node (ref "IMU") (pin "P$3") (pinfunction "MISO_P$3") (pintype "bidirectional"))
      (node (ref "U2") (pin "35") (pinfunction "PB14-SPI2MISO/USART3RTS/TIM1CH2N_35") (pintype "bidirectional"))
    )
    (net (code "28") (name "IMU_SPI_MOSI") (class "Default")
      (node (ref "IMU") (pin "P$4") (pinfunction "MOSI_P$4") (pintype "bidirectional"))
      (node (ref "U2") (pin "36") (pinfunction "PB15-SPI2MOSI/I2S2SD/TIM1CH3N_36") (pintype "bidirectional"))
    )
    (net (code "29") (name "IMU_SPI_SCK") (class "Default")
      (node (ref "IMU") (pin "P$5") (pinfunction "SCK_P$5") (pintype "bidirectional"))
      (node (ref "U2") (pin "34") (pinfunction "PB13-SPI2SCK/I2S2CK/USART3CTS/TIM1CH1N/CAN2TX/ETH_(R)MII_TXD1_34") (pintype "bidirectional"))
    )
    (net (code "30") (name "JTAG_RST") (class "Default")
      (node (ref "C27") (pin "P$2") (pinfunction "2_P$2") (pintype "passive"))
      (node (ref "JTAG") (pin "10") (pinfunction "10_10") (pintype "bidirectional"))
      (node (ref "R7") (pin "P$1") (pinfunction "1_P$1") (pintype "passive"))
      (node (ref "U2") (pin "7") (pinfunction "NRST_7") (pintype "bidirectional"))
    )
    (net (code "31") (name "JTAG_TCK") (class "Default")
      (node (ref "JTAG") (pin "4") (pinfunction "4_4") (pintype "bidirectional"))
      (node (ref "U2") (pin "49") (pinfunction "PA14/JTCK/SWCLK_49") (pintype "bidirectional"))
    )
    (net (code "32") (name "JTAG_TDI") (class "Default")
      (node (ref "JTAG") (pin "8") (pinfunction "8_8") (pintype "bidirectional"))
      (node (ref "U2") (pin "50") (pinfunction "PA15/JTDI-SPI3NSS/I2S3WS-TIM2CH1ETR/SPI1NSS_50") (pintype "bidirectional"))
    )
    (net (code "33") (name "JTAG_TDO") (class "Default")
      (node (ref "JTAG") (pin "6") (pinfunction "6_6") (pintype "bidirectional"))
      (node (ref "U2") (pin "55") (pinfunction "PB3/JTDO-SPI3SCK/I2S3CK-TIM2CH2/TRACESWO/SPI1SCK_55") (pintype "bidirectional"))
    )
    (net (code "34") (name "JTAG_TMS") (class "Default")
      (node (ref "JTAG") (pin "2") (pinfunction "2_2") (pintype "bidirectional"))
      (node (ref "U2") (pin "46") (pinfunction "PA13/JTMS/SWDIO_46") (pintype "bidirectional"))
    )
    (net (code "35") (name "JTAG_TRST") (class "Default")
      (node (ref "LED1") (pin "C") (pinfunction "C_C") (pintype "passive"))
      (node (ref "U2") (pin "56") (pinfunction "PB4/JNTRST-SPI3MISO-TIM3CH1/SPI1MISO_56") (pintype "bidirectional"))
      (node (ref "X1") (pin "5") (pinfunction "5_5") (pintype "bidirectional"))
    )
    (net (code "36") (name "LT_I2C1_SCL") (class "Default")
      (node (ref "CON_CAN/I2C1") (pin "6") (pinfunction "6_6") (pintype "bidirectional"))
      (node (ref "LT_I2C2") (pin "6") (pinfunction "SCL2_6") (pintype "bidirectional"))
      (node (ref "R3") (pin "P$2") (pinfunction "2_P$2") (pintype "passive"))
      (node (ref "R44") (pin "P$1") (pinfunction "1_P$1") (pintype "passive"))
    )
    (net (code "37") (name "LT_I2C1_SDA") (class "Default")
      (node (ref "CON_CAN/I2C1") (pin "7") (pinfunction "7_7") (pintype "bidirectional"))
      (node (ref "LT_I2C2") (pin "5") (pinfunction "SDA2_5") (pintype "bidirectional"))
      (node (ref "R43") (pin "P$1") (pinfunction "1_P$1") (pintype "passive"))
      (node (ref "R6") (pin "P$2") (pinfunction "2_P$2") (pintype "passive"))
    )
    (net (code "38") (name "NC_1") (class "Default")
      (node (ref "U$1") (pin "P$1") (pinfunction "SBUS1_P$1") (pintype "bidirectional"))
    )
    (net (code "39") (name "Net-(C13-1)") (class "Default")
      (node (ref "C13") (pin "P$1") (pinfunction "1_P$1") (pintype "passive"))
      (node (ref "IC9") (pin "4") (pinfunction "BYPASS_4") (pintype "bidirectional"))
    )
    (net (code "40") (name "Net-(C15-1)") (class "Default")
      (node (ref "C15") (pin "P$1") (pinfunction "1_P$1") (pintype "passive"))
      (node (ref "LT_I2C2") (pin "7") (pinfunction "VREF2_7") (pintype "bidirectional"))
      (node (ref "LT_I2C2") (pin "8") (pinfunction "EN_8") (pintype "bidirectional"))
      (node (ref "R25") (pin "P$1") (pinfunction "1_P$1") (pintype "passive"))
    )
    (net (code "41") (name "Net-(C31-2)") (class "Default")
      (node (ref "C28") (pin "+") (pinfunction "+_+") (pintype "passive"))
      (node (ref "C31") (pin "P$2") (pinfunction "2_P$2") (pintype "passive"))
      (node (ref "L1") (pin "P$2") (pinfunction "2_P$2") (pintype "passive"))
      (node (ref "U2") (pin "13") (pinfunction "VDDA_13") (pintype "power_in"))
    )
    (net (code "42") (name "Net-(C35-1)") (class "Default")
      (node (ref "C35") (pin "P$1") (pinfunction "1_P$1") (pintype "passive"))
      (node (ref "VREG1") (pin "4") (pinfunction "BYP_4") (pintype "bidirectional"))
    )
    (net (code "43") (name "Net-(C42-2)") (class "Default")
      (node (ref "C42") (pin "P$2") (pinfunction "2_P$2") (pintype "passive"))
      (node (ref "R58") (pin "P$2") (pinfunction "2_P$2") (pintype "passive"))
      (node (ref "R59") (pin "P$1") (pinfunction "1_P$1") (pintype "passive"))
      (node (ref "R60") (pin "P$2") (pinfunction "2_P$2") (pintype "passive"))
      (node (ref "R61") (pin "P$1") (pinfunction "1_P$1") (pintype "passive"))
    )
    (net (code "44") (name "Net-(CON_USB-2)") (class "Default")
      (node (ref "CON_USB") (pin "PIN_2") (pinfunction "2_PIN_2") (pintype "input"))
      (node (ref "R1") (pin "P$1") (pinfunction "1_P$1") (pintype "passive"))
    )
    (net (code "45") (name "Net-(CON_USB-3)") (class "Default")
      (node (ref "CON_USB") (pin "PIN_3") (pinfunction "3_PIN_3") (pintype "input"))
      (node (ref "R2") (pin "P$1") (pinfunction "1_P$1") (pintype "passive"))
    )
    (net (code "46") (name "Net-(Q2-C)") (class "Default")
      (node (ref "Q2") (pin "3") (pinfunction "C_3") (pintype "passive"))
      (node (ref "R14") (pin "P$2") (pinfunction "2_P$2") (pintype "passive"))
    )
    (net (code "47") (name "Net-(R8-1)") (class "Default")
      (node (ref "LED1") (pin "A") (pinfunction "A_A") (pintype "passive"))
      (node (ref "R8") (pin "P$1") (pinfunction "1_P$1") (pintype "passive"))
    )
    (net (code "48") (name "Net-(R19-2)") (class "Default")
      (node (ref "CON_UART2") (pin "2") (pinfunction "2_2") (pintype "bidirectional"))
      (node (ref "R19") (pin "P$2") (pinfunction "2_P$2") (pintype "passive"))
      (node (ref "R20") (pin "P$2") (pinfunction "2_P$2") (pintype "passive"))
    )
    (net (code "49") (name "Net-(R21-2)") (class "Default")
      (node (ref "CON_UART1") (pin "2") (pinfunction "2_2") (pintype "bidirectional"))
      (node (ref "R21") (pin "P$2") (pinfunction "2_P$2") (pintype "passive"))
      (node (ref "R22") (pin "P$2") (pinfunction "2_P$2") (pintype "passive"))
    )
    (net (code "50") (name "Net-(R23-1)") (class "Default")
      (node (ref "LED4") (pin "A") (pinfunction "A_A") (pintype "passive"))
      (node (ref "R23") (pin "P$1") (pinfunction "1_P$1") (pintype "passive"))
    )
    (net (code "51") (name "Net-(R32-1)") (class "Default")
      (node (ref "LED3") (pin "A") (pinfunction "A_A") (pintype "passive"))
      (node (ref "R32") (pin "P$1") (pinfunction "1_P$1") (pintype "passive"))
    )
    (net (code "52") (name "Net-(R35-1)") (class "Default")
      (node (ref "LED5") (pin "A") (pinfunction "A_A") (pintype "passive"))
      (node (ref "R35") (pin "P$1") (pinfunction "1_P$1") (pintype "passive"))
    )
    (net (code "53") (name "Net-(R36-1)") (class "Default")
      (node (ref "LED6") (pin "A") (pinfunction "A_A") (pintype "passive"))
      (node (ref "R36") (pin "P$1") (pinfunction "1_P$1") (pintype "passive"))
    )
    (net (code "54") (name "Net-(R37-1)") (class "Default")
      (node (ref "LED7") (pin "A") (pinfunction "A_A") (pintype "passive"))
      (node (ref "R37") (pin "P$1") (pinfunction "1_P$1") (pintype "passive"))
    )
    (net (code "55") (name "Net-(R38-1)") (class "Default")
      (node (ref "LED8") (pin "A") (pinfunction "A_A") (pintype "passive"))
      (node (ref "R38") (pin "P$1") (pinfunction "1_P$1") (pintype "passive"))
    )
    (net (code "56") (name "Net-(R55-2)") (class "Default")
      (node (ref "R55") (pin "P$2") (pinfunction "2_P$2") (pintype "passive"))
      (node (ref "R56") (pin "P$1") (pinfunction "1_P$1") (pintype "passive"))
      (node (ref "U1") (pin "8") (pinfunction "RS_8") (pintype "input"))
    )
    (net (code "57") (name "OSC_IN") (class "Default")
      (node (ref "C4") (pin "P$2") (pinfunction "2_P$2") (pintype "passive"))
      (node (ref "Q1") (pin "P$3") (pinfunction "P$3_P$3") (pintype "bidirectional"))
      (node (ref "U2") (pin "5") (pinfunction "PD0-OSC_IN-CAN1RX_5") (pintype "input"))
    )
    (net (code "58") (name "OSC_OUT") (class "Default")
      (node (ref "C6") (pin "P$1") (pinfunction "1_P$1") (pintype "passive"))
      (node (ref "Q1") (pin "P$1") (pinfunction "P$1_P$1") (pintype "bidirectional"))
      (node (ref "U2") (pin "6") (pinfunction "PD1-OSC_OUT-CAN1TX_6") (pintype "output"))
    )
    (net (code "59") (name "PC10") (class "Default")
      (node (ref "U2") (pin "51") (pinfunction "PC10-USART4TX-USART3TX/SPI3SCK/I2S3CK_51") (pintype "bidirectional"))
      (node (ref "X1") (pin "3") (pinfunction "3_3") (pintype "bidirectional"))
    )
    (net (code "60") (name "PC12") (class "Default")
      (node (ref "U2") (pin "53") (pinfunction "PC12-USART5TX-USART3CK/SPI3MOSI/I2S3SD_53") (pintype "bidirectional"))
      (node (ref "X1") (pin "4") (pinfunction "4_4") (pintype "bidirectional"))
    )
    (net (code "61") (name "SERVO_1") (class "Default")
      (node (ref "U$1") (pin "P$11") (pinfunction "S1_P$11") (pintype "bidirectional"))
      (node (ref "U2") (pin "37") (pinfunction "PC6-I2S2MCK-TIM3CH1_37") (pintype "bidirectional"))
    )
    (net (code "62") (name "SERVO_2") (class "Default")
      (node (ref "U$1") (pin "P$10") (pinfunction "S2_P$10") (pintype "bidirectional"))
      (node (ref "U2") (pin "38") (pinfunction "PC7-I2S3MCK-TIM3CH2_38") (pintype "bidirectional"))
    )
    (net (code "63") (name "SERVO_3") (class "Default")
      (node (ref "U$1") (pin "P$9") (pinfunction "S3_P$9") (pintype "bidirectional"))
      (node (ref "U2") (pin "39") (pinfunction "PC8-TIM3CH3_39") (pintype "bidirectional"))
    )
    (net (code "64") (name "SERVO_4") (class "Default")
      (node (ref "U$1") (pin "P$8") (pinfunction "S4_P$8") (pintype "bidirectional"))
      (node (ref "U2") (pin "40") (pinfunction "PC9-TIM3CH4_40") (pintype "bidirectional"))
    )
    (net (code "65") (name "SERVO_5") (class "Default")
      (node (ref "U$1") (pin "P$7") (pinfunction "S5_P$7") (pintype "bidirectional"))
      (node (ref "U2") (pin "14") (pinfunction "PA0-WKUP/USART2CTS/ADC0/TIM2CH1ETR/TIM5CH1/ETH_MII_CRS_WKUP_14") (pintype "bidirectional"))
    )
    (net (code "66") (name "SERVO_6") (class "Default")
      (node (ref "U$1") (pin "P$6") (pinfunction "S6_P$6") (pintype "bidirectional"))
      (node (ref "U2") (pin "15") (pinfunction "PA1-USART2RTS/ADC1/TIM5CH2/TIM2CH2/ETH_MII_RX_CLK/ETH_RMII_REF_CLK_15") (pintype "bidirectional"))
    )
    (net (code "67") (name "SERVO_7{slash}I2C1_SCL") (class "Default")
      (node (ref "LT_I2C2") (pin "3") (pinfunction "SCL1_3") (pintype "bidirectional"))
      (node (ref "R3") (pin "P$1") (pinfunction "1_P$1") (pintype "passive"))
      (node (ref "R33") (pin "P$1") (pinfunction "1_P$1") (pintype "passive"))
      (node (ref "U$1") (pin "P$5") (pinfunction "S7_P$5") (pintype "bidirectional"))
      (node (ref "U2") (pin "58") (pinfunction "PB6-I2C1SCL/TIM4CH1-USART1TX/CAN2TX_58") (pintype "bidirectional"))
    )
    (net (code "68") (name "SERVO_8{slash}I2C1_SDA") (class "Default")
      (node (ref "LT_I2C2") (pin "4") (pinfunction "SDA1_4") (pintype "bidirectional"))
      (node (ref "R34") (pin "P$1") (pinfunction "1_P$1") (pintype "passive"))
      (node (ref "R6") (pin "P$1") (pinfunction "1_P$1") (pintype "passive"))
      (node (ref "U2") (pin "59") (pinfunction "PB7-I2C1SDA/TIM4CH2-USART1RX_59") (pintype "bidirectional"))
    )
    (net (code "69") (name "SERVO_BUS") (class "Default")
      (node (ref "R16") (pin "P$1") (pinfunction "1_P$1") (pintype "passive"))
      (node (ref "U$1") (pin "P$3") (pinfunction "SBUS2_P$3") (pintype "bidirectional"))
    )
    (net (code "70") (name "UART1_RX") (class "Default")
      (node (ref "CON_UART1") (pin "4") (pinfunction "4_4") (pintype "bidirectional"))
      (node (ref "R24") (pin "P$2") (pinfunction "2_P$2") (pintype "passive"))
      (node (ref "U2") (pin "43") (pinfunction "PA10-USART1RX/TIM1CH3/OTG_FS_ID_43") (pintype "bidirectional"))
    )
    (net (code "71") (name "UART1_TX") (class "Default")
      (node (ref "CON_UART1") (pin "3") (pinfunction "3_3") (pintype "bidirectional"))
      (node (ref "U2") (pin "42") (pinfunction "PA9-USART1TX/TIM1CH2/OTG_FS_VBUS_42") (pintype "bidirectional"))
    )
    (net (code "72") (name "UART2_RX") (class "Default")
      (node (ref "CON_UART2") (pin "4") (pinfunction "4_4") (pintype "bidirectional"))
      (node (ref "R26") (pin "P$2") (pinfunction "2_P$2") (pintype "passive"))
      (node (ref "U2") (pin "17") (pinfunction "PA3-USART2RX/TIM5CH4/ADC3/TIM2CH4/ETH_MII_COL_17") (pintype "bidirectional"))
    )
    (net (code "73") (name "UART2_TX") (class "Default")
      (node (ref "CON_UART2") (pin "3") (pinfunction "3_3") (pintype "bidirectional"))
      (node (ref "U2") (pin "16") (pinfunction "PA2-USART2TX/TIM5CH3/ADC2/TIM2CH3/ETH_(R)MII_MDIO_16") (pintype "bidirectional"))
    )
    (net (code "74") (name "UART3_RX") (class "Default")
      (node (ref "CON_UART3/5") (pin "3") (pinfunction "3_3") (pintype "bidirectional"))
      (node (ref "U2") (pin "52") (pinfunction "PC11-USART4RX-USART3RX/SPI3MISO_52") (pintype "bidirectional"))
    )
    (net (code "75") (name "UART5_RX") (class "Default")
      (node (ref "CON_UART3/5") (pin "6") (pinfunction "6_6") (pintype "bidirectional"))
      (node (ref "U2") (pin "54") (pinfunction "PD2-TIM3ETR/USART5RX_54") (pintype "bidirectional"))
    )
    (net (code "76") (name "USB_DETECT") (class "Default")
      (node (ref "R12") (pin "P$2") (pinfunction "2_P$2") (pintype "passive"))
      (node (ref "R13") (pin "P$1") (pinfunction "1_P$1") (pintype "passive"))
      (node (ref "U2") (pin "41") (pinfunction "PA8-USART1CK/OTG_FS_SOF/MCO/TIM1CH1_41") (pintype "bidirectional"))
    )
    (net (code "77") (name "USB_DISC") (class "Default")
      (node (ref "Q2") (pin "1") (pinfunction "B_1") (pintype "passive"))
      (node (ref "U2") (pin "4") (pinfunction "PC15-OSC32_OUT_4") (pintype "bidirectional"))
    )
    (net (code "78") (name "USB_DM") (class "Default")
      (node (ref "R1") (pin "P$2") (pinfunction "2_P$2") (pintype "passive"))
      (node (ref "R27") (pin "P$2") (pinfunction "2_P$2") (pintype "passive"))
      (node (ref "U2") (pin "44") (pinfunction "PA11-USART1CTS/CAN1RX/OTG_FS_DM/TIM1CH4_44") (pintype "bidirectional"))
    )
    (net (code "79") (name "USB_DP") (class "Default")
      (node (ref "R14") (pin "P$1") (pinfunction "1_P$1") (pintype "passive"))
      (node (ref "R2") (pin "P$2") (pinfunction "2_P$2") (pintype "passive"))
      (node (ref "R28") (pin "P$2") (pinfunction "2_P$2") (pintype "passive"))
      (node (ref "U2") (pin "45") (pinfunction "PA12-USART1RTS/CAN1TX/OTG_FS_DP/TIM1ETR_45") (pintype "bidirectional"))
    )
    (net (code "80") (name "USB_VBUS") (class "Default")
      (node (ref "CON_USB") (pin "PIN_1") (pinfunction "1_PIN_1") (pintype "input"))
      (node (ref "D3") (pin "A") (pinfunction "A_A") (pintype "passive"))
      (node (ref "R12") (pin "P$1") (pinfunction "1_P$1") (pintype "passive"))
    )
    (net (code "81") (name "VREF") (class "Default")
      (node (ref "U1") (pin "5") (pinfunction "VREF_5") (pintype "power_in"))
    )
    (net (code "82") (name "V_BAT") (class "Default")
      (node (ref "CON_CAN/I2C1") (pin "2") (pinfunction "2_2") (pintype "bidirectional"))
      (node (ref "R11") (pin "P$2") (pinfunction "2_P$2") (pintype "passive"))
      (node (ref "R17") (pin "P$1") (pinfunction "1_P$1") (pintype "passive"))
    )
    (net (code "83") (name "V_BAT_MEAS") (class "Default")
      (node (ref "R17") (pin "P$2") (pinfunction "2_P$2") (pintype "passive"))
      (node (ref "R18") (pin "P$1") (pinfunction "1_P$1") (pintype "passive"))
      (node (ref "U2") (pin "24") (pinfunction "PC4-ADC14/ETH_(R)MII_RXD0_24") (pintype "bidirectional"))
    )
    (net (code "84") (name "V_IN") (class "Default")
      (node (ref "C3") (pin "P$1") (pinfunction "1_P$1") (pintype "passive"))
      (node (ref "C38") (pin "P$1") (pinfunction "1_P$1") (pintype "passive"))
      (node (ref "C39") (pin "+") (pinfunction "+_+") (pintype "passive"))
      (node (ref "CON_CAN/I2C1") (pin "3") (pinfunction "3_3") (pintype "bidirectional"))
      (node (ref "D3") (pin "C") (pinfunction "C_C") (pintype "passive"))
      (node (ref "IC9") (pin "1") (pinfunction "VIN_1") (pintype "bidirectional"))
      (node (ref "IC9") (pin "3") (pinfunction "ON/OFF_3") (pintype "bidirectional"))
      (node (ref "IMU") (pin "P$2") (pinfunction "VCC_P$2") (pintype "bidirectional"))
      (node (ref "R11") (pin "P$1") (pinfunction "1_P$1") (pintype "passive"))
      (node (ref "R15") (pin "P$1") (pinfunction "1_P$1") (pintype "passive"))
      (node (ref "R16") (pin "P$2") (pinfunction "2_P$2") (pintype "passive"))
      (node (ref "R20") (pin "P$1") (pinfunction "1_P$1") (pintype "passive"))
      (node (ref "R22") (pin "P$1") (pinfunction "1_P$1") (pintype "passive"))
      (node (ref "R23") (pin "P$2") (pinfunction "2_P$2") (pintype "passive"))
      (node (ref "VREG1") (pin "1") (pinfunction "ENABLE_1") (pintype "bidirectional"))
      (node (ref "VREG1") (pin "2") (pinfunction "VIN_2") (pintype "bidirectional"))
    )
    (net (code "85") (name "unconnected-(CON_USB-4-PadPIN_4)") (class "Default")
      (node (ref "CON_USB") (pin "PIN_4") (pinfunction "4_PIN_4") (pintype "input"))
    )
    (net (code "86") (name "unconnected-(CON_USB-S1-PadGND_LEFT)") (class "Default")
      (node (ref "CON_USB") (pin "GND_LEFT") (pinfunction "S1_GND_LEFT") (pintype "passive"))
    )
    (net (code "87") (name "unconnected-(CON_USB-S2-PadGND_RIGHT)") (class "Default")
      (node (ref "CON_USB") (pin "GND_RIGHT") (pinfunction "S2_GND_RIGHT") (pintype "passive"))
    )
    (net (code "88") (name "unconnected-(CON_USB-S3-PadGND_UP_LEFT)") (class "Default")
      (node (ref "CON_USB") (pin "GND_UP_LEFT") (pinfunction "S3_GND_UP_LEFT") (pintype "passive"))
    )
    (net (code "89") (name "unconnected-(CON_USB-S4-PadGND_UP_RIGHT)") (class "Default")
      (node (ref "CON_USB") (pin "GND_UP_RIGHT") (pinfunction "S4_GND_UP_RIGHT") (pintype "passive"))
    )
    (net (code "90") (name "unconnected-(U3-~{XCLR}-Pad8)") (class "Default")
      (node (ref "U3") (pin "8") (pinfunction "~{XCLR}_8") (pintype "input"))
    )
  )
)
